# ProPrj_USB_Connector_2025-08-25.net
KiCad netlist of a schematic drawn in EasyEDA Pro
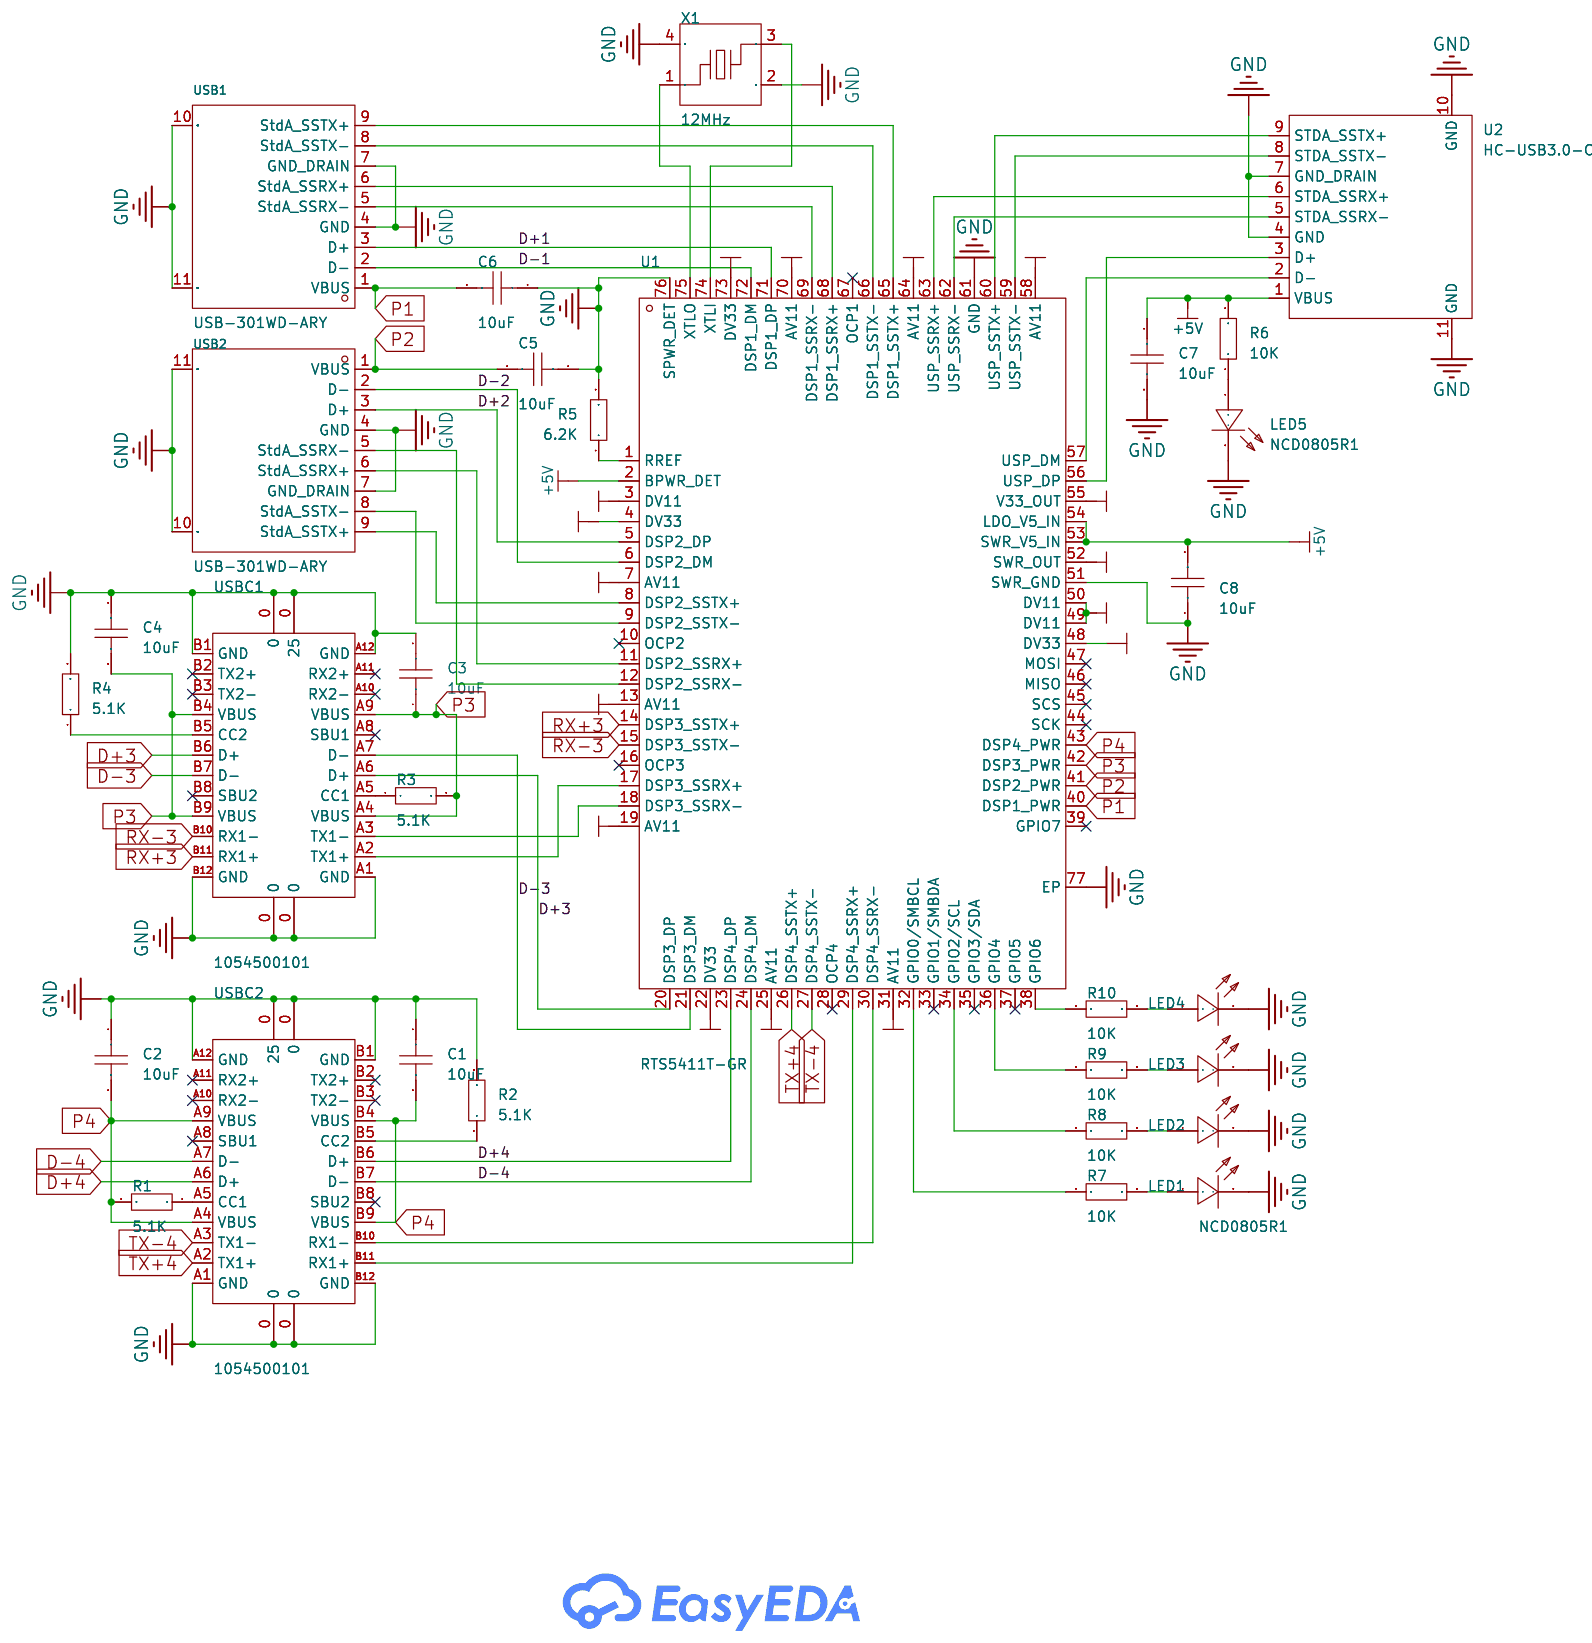
[diagram p0: schematic sheet]

(export (version "E")
  (design (tool "Eeschema 10.0.6"))
  (components
    (comp (ref "C1")
      (value "10uF")
      (footprint "easyedapro:C0603")
      (libsource (lib "easyedapro") (part "CAP"))
    )
    (comp (ref "C2")
      (value "10uF")
      (footprint "easyedapro:C0603")
      (libsource (lib "easyedapro") (part "CAP"))
    )
    (comp (ref "C3")
      (value "10uF")
      (footprint "easyedapro:C0603")
      (libsource (lib "easyedapro") (part "CAP"))
    )
    (comp (ref "C4")
      (value "10uF")
      (footprint "easyedapro:C0603")
      (libsource (lib "easyedapro") (part "CAP"))
    )
    (comp (ref "C5")
      (value "10uF")
      (footprint "easyedapro:C0603")
      (libsource (lib "easyedapro") (part "CAP"))
    )
    (comp (ref "C6")
      (value "10uF")
      (footprint "easyedapro:C0603")
      (libsource (lib "easyedapro") (part "CAP"))
    )
    (comp (ref "C7")
      (value "10uF")
      (footprint "easyedapro:C0603")
      (libsource (lib "easyedapro") (part "CAP"))
    )
    (comp (ref "C8")
      (value "10uF")
      (footprint "easyedapro:C0603")
      (libsource (lib "easyedapro") (part "CAP"))
    )
    (comp (ref "LED1")
      (value "NCD0805R1")
      (footprint "easyedapro:LED0805-R-RD")
      (fields (field (name "Manufacturer") "国星光电"))
      (libsource (lib "easyedapro") (part "FC-2012HRK-620D"))
    )
    (comp (ref "LED2")
      (value "NCD0805R1")
      (footprint "easyedapro:LED0805-R-RD")
      (fields (field (name "Manufacturer") "国星光电"))
      (libsource (lib "easyedapro") (part "FC-2012HRK-620D"))
    )
    (comp (ref "LED3")
      (value "NCD0805R1")
      (footprint "easyedapro:LED0805-R-RD")
      (fields (field (name "Manufacturer") "国星光电"))
      (libsource (lib "easyedapro") (part "FC-2012HRK-620D"))
    )
    (comp (ref "LED4")
      (value "NCD0805R1")
      (footprint "easyedapro:LED0805-R-RD")
      (fields (field (name "Manufacturer") "国星光电"))
      (libsource (lib "easyedapro") (part "FC-2012HRK-620D"))
    )
    (comp (ref "LED5")
      (value "NCD0805R1")
      (footprint "easyedapro:LED0805-R-RD")
      (fields (field (name "Manufacturer") "国星光电"))
      (libsource (lib "easyedapro") (part "FC-2012HRK-620D"))
    )
    (comp (ref "R1")
      (value "5.1K")
      (footprint "easyedapro:R0603")
      (libsource (lib "easyedapro") (part "Res"))
    )
    (comp (ref "R2")
      (value "5.1K")
      (footprint "easyedapro:R0603")
      (libsource (lib "easyedapro") (part "Res"))
    )
    (comp (ref "R3")
      (value "5.1K")
      (footprint "easyedapro:R0603")
      (libsource (lib "easyedapro") (part "Res"))
    )
    (comp (ref "R4")
      (value "5.1K")
      (footprint "easyedapro:R0603")
      (libsource (lib "easyedapro") (part "Res"))
    )
    (comp (ref "R5")
      (value "6.2K")
      (footprint "easyedapro:R0603")
      (libsource (lib "easyedapro") (part "Res"))
    )
    (comp (ref "R6") (value "10K") (footprint "easyedapro:R0603") (libsource (lib "easyedapro") (part "Res")))
    (comp (ref "R7") (value "10K") (footprint "easyedapro:R0603") (libsource (lib "easyedapro") (part "Res")))
    (comp (ref "R8") (value "10K") (footprint "easyedapro:R0603") (libsource (lib "easyedapro") (part "Res")))
    (comp (ref "R9") (value "10K") (footprint "easyedapro:R0603") (libsource (lib "easyedapro") (part "Res")))
    (comp (ref "R10")
      (value "10K")
      (footprint "easyedapro:R0603")
      (libsource (lib "easyedapro") (part "Res"))
    )
    (comp (ref "U1")
      (value "RTS5411T-GR")
      (footprint "easyedapro:QFN-76_L9.0-W9.0-P0.40-BL-EP5.4")
      (fields (field (name "Manufacturer") "REALTEK(瑞昱)"))
      (libsource (lib "easyedapro") (part "RTS5411T-GR"))
    )
    (comp (ref "U2")
      (value "HC-USB3.0-C26")
      (footprint "easyedapro:USB-3.0-A-SMD_HC-USB3.0-C26")
      (fields (field (name "Manufacturer") "HC(虹成电子)"))
      (libsource (lib "easyedapro") (part "HC-USB3.0-C26"))
    )
    (comp (ref "USB1")
      (value "USB-301WD-ARY")
      (footprint "easyedapro:USB-TH_XUNPU_USB-301WD-ARY")
      (fields (field (name "Manufacturer") "XUNPU(讯普)"))
      (libsource (lib "easyedapro") (part "USB-301WD-ARY"))
    )
    (comp (ref "USB2")
      (value "USB-301WD-ARY")
      (footprint "easyedapro:USB-TH_XUNPU_USB-301WD-ARY")
      (fields (field (name "Manufacturer") "XUNPU(讯普)"))
      (libsource (lib "easyedapro") (part "USB-301WD-ARY"))
    )
    (comp (ref "USBC1")
      (value "1054500101")
      (footprint "easyedapro:USB-C-SMD_TYPE-C-USB-18")
      (fields (field (name "Manufacturer") "MOLEX"))
      (libsource (lib "easyedapro") (part "105450-0101"))
    )
    (comp (ref "USBC2")
      (value "1054500101")
      (footprint "easyedapro:USB-C-SMD_TYPE-C-USB-18")
      (fields (field (name "Manufacturer") "MOLEX"))
      (libsource (lib "easyedapro") (part "105450-0101"))
    )
    (comp (ref "X1")
      (value "12MHz")
      (footprint "easyedapro:CRYSTAL-SMD_4P-L3.2-W2.5-BL-1")
      (fields
        (field (name "Manufacturer Part") "XL2EL89COI-111YLC-12M")
        (field (name "Manufacturer") "YXC(扬兴晶振)")
      )
      (libsource (lib "easyedapro") (part "XL2EL89COI-111YLC-12M"))
    )
  )
  (nets
    (net (code "1") (name "+1V1") (class "Default")
      (node (ref "U1") (pin "13") (pinfunction "AV11_13") (pintype "unspecified"))
      (node (ref "U1") (pin "19") (pinfunction "AV11_19") (pintype "unspecified"))
      (node (ref "U1") (pin "25") (pinfunction "AV11_25") (pintype "unspecified"))
      (node (ref "U1") (pin "3") (pinfunction "DV11_3") (pintype "unspecified"))
      (node (ref "U1") (pin "31") (pinfunction "AV11_31") (pintype "unspecified"))
      (node (ref "U1") (pin "49") (pinfunction "DV11_49") (pintype "unspecified"))
      (node (ref "U1") (pin "50") (pinfunction "DV11_50") (pintype "unspecified"))
      (node (ref "U1") (pin "52") (pinfunction "SWR_OUT_52") (pintype "unspecified"))
      (node (ref "U1") (pin "58") (pinfunction "AV11_58") (pintype "unspecified"))
      (node (ref "U1") (pin "64") (pinfunction "AV11_64") (pintype "unspecified"))
      (node (ref "U1") (pin "7") (pinfunction "AV11_7") (pintype "unspecified"))
      (node (ref "U1") (pin "70") (pinfunction "AV11_70") (pintype "unspecified"))
    )
    (net (code "2") (name "+3V3") (class "Default")
      (node (ref "U1") (pin "22") (pinfunction "DV33_22") (pintype "unspecified"))
      (node (ref "U1") (pin "4") (pinfunction "DV33_4") (pintype "unspecified"))
      (node (ref "U1") (pin "48") (pinfunction "DV33_48") (pintype "unspecified"))
      (node (ref "U1") (pin "55") (pinfunction "V33_OUT_55") (pintype "unspecified"))
      (node (ref "U1") (pin "73") (pinfunction "DV33_73") (pintype "unspecified"))
    )
    (net (code "3") (name "+5V") (class "Default")
      (node (ref "C7") (pin "1") (pinfunction "1_1") (pintype "input"))
      (node (ref "C8") (pin "2") (pinfunction "2_2") (pintype "input"))
      (node (ref "R6") (pin "2") (pinfunction "2_2") (pintype "input"))
      (node (ref "U1") (pin "2") (pinfunction "BPWR_DET_2") (pintype "unspecified"))
      (node (ref "U1") (pin "53") (pinfunction "SWR_V5_IN_53") (pintype "unspecified"))
      (node (ref "U1") (pin "54") (pinfunction "LDO_V5_IN_54") (pintype "unspecified"))
      (node (ref "U2") (pin "1") (pinfunction "VBUS_1") (pintype "unspecified"))
    )
    (net (code "4") (name "/D+1") (class "Default")
      (node (ref "U1") (pin "71") (pinfunction "DSP1_DP_71") (pintype "unspecified"))
      (node (ref "USB1") (pin "3") (pinfunction "D+_3") (pintype "input"))
    )
    (net (code "5") (name "/D+2") (class "Default")
      (node (ref "U1") (pin "5") (pinfunction "DSP2_DP_5") (pintype "unspecified"))
      (node (ref "USB2") (pin "3") (pinfunction "D+_3") (pintype "input"))
    )
    (net (code "6") (name "/D-1") (class "Default")
      (node (ref "U1") (pin "72") (pinfunction "DSP1_DM_72") (pintype "unspecified"))
      (node (ref "USB1") (pin "2") (pinfunction "D-_2") (pintype "input"))
    )
    (net (code "7") (name "/D-2") (class "Default")
      (node (ref "U1") (pin "6") (pinfunction "DSP2_DM_6") (pintype "unspecified"))
      (node (ref "USB2") (pin "2") (pinfunction "D-_2") (pintype "input"))
    )
    (net (code "8") (name "D+3") (class "Default")
      (node (ref "U1") (pin "20") (pinfunction "DSP3_DP_20") (pintype "unspecified"))
      (node (ref "USBC1") (pin "A6") (pinfunction "D+_A6") (pintype "unspecified"))
      (node (ref "USBC1") (pin "B6") (pinfunction "D+_B6") (pintype "unspecified"))
    )
    (net (code "9") (name "D+4") (class "Default")
      (node (ref "U1") (pin "23") (pinfunction "DSP4_DP_23") (pintype "unspecified"))
      (node (ref "USBC2") (pin "A6") (pinfunction "D+_A6") (pintype "unspecified"))
      (node (ref "USBC2") (pin "B6") (pinfunction "D+_B6") (pintype "unspecified"))
    )
    (net (code "10") (name "D-3") (class "Default")
      (node (ref "U1") (pin "21") (pinfunction "DSP3_DM_21") (pintype "unspecified"))
      (node (ref "USBC1") (pin "A7") (pinfunction "D-_A7") (pintype "unspecified"))
      (node (ref "USBC1") (pin "B7") (pinfunction "D-_B7") (pintype "unspecified"))
    )
    (net (code "11") (name "D-4") (class "Default")
      (node (ref "U1") (pin "24") (pinfunction "DSP4_DM_24") (pintype "unspecified"))
      (node (ref "USBC2") (pin "A7") (pinfunction "D-_A7") (pintype "unspecified"))
      (node (ref "USBC2") (pin "B7") (pinfunction "D-_B7") (pintype "unspecified"))
    )
    (net (code "12") (name "GND") (class "Default")
      (node (ref "C1") (pin "1") (pinfunction "1_1") (pintype "input"))
      (node (ref "C2") (pin "1") (pinfunction "1_1") (pintype "input"))
      (node (ref "C3") (pin "2") (pinfunction "2_2") (pintype "input"))
      (node (ref "C4") (pin "1") (pinfunction "1_1") (pintype "input"))
      (node (ref "C5") (pin "1") (pinfunction "1_1") (pintype "input"))
      (node (ref "C6") (pin "1") (pinfunction "1_1") (pintype "input"))
      (node (ref "C7") (pin "2") (pinfunction "2_2") (pintype "input"))
      (node (ref "C8") (pin "1") (pinfunction "1_1") (pintype "input"))
      (node (ref "LED1") (pin "2") (pinfunction "-_2") (pintype "unspecified"))
      (node (ref "LED2") (pin "2") (pinfunction "-_2") (pintype "unspecified"))
      (node (ref "LED3") (pin "2") (pinfunction "-_2") (pintype "unspecified"))
      (node (ref "LED4") (pin "2") (pinfunction "-_2") (pintype "unspecified"))
      (node (ref "LED5") (pin "2") (pinfunction "-_2") (pintype "unspecified"))
      (node (ref "R2") (pin "2") (pinfunction "2_2") (pintype "input"))
      (node (ref "R4") (pin "2") (pinfunction "2_2") (pintype "input"))
      (node (ref "R5") (pin "2") (pinfunction "2_2") (pintype "input"))
      (node (ref "U1") (pin "51") (pinfunction "SWR_GND_51") (pintype "unspecified"))
      (node (ref "U1") (pin "61") (pinfunction "GND_61") (pintype "unspecified"))
      (node (ref "U1") (pin "76") (pinfunction "SPWR_DET_76") (pintype "unspecified"))
      (node (ref "U1") (pin "77") (pinfunction "EP_77") (pintype "unspecified"))
      (node (ref "U2") (pin "10") (pinfunction "GND_10") (pintype "unspecified"))
      (node (ref "U2") (pin "11") (pinfunction "GND_11") (pintype "unspecified"))
      (node (ref "U2") (pin "4") (pinfunction "GND_4") (pintype "unspecified"))
      (node (ref "U2") (pin "7") (pinfunction "GND_DRAIN_7") (pintype "unspecified"))
      (node (ref "USB1") (pin "10") (pinfunction "SHIELD_10") (pintype "input"))
      (node (ref "USB1") (pin "11") (pinfunction "SHIELD_11") (pintype "input"))
      (node (ref "USB1") (pin "4") (pinfunction "GND_4") (pintype "input"))
      (node (ref "USB1") (pin "7") (pinfunction "GND_DRAIN_7") (pintype "input"))
      (node (ref "USB2") (pin "10") (pinfunction "SHIELD_10") (pintype "input"))
      (node (ref "USB2") (pin "11") (pinfunction "SHIELD_11") (pintype "input"))
      (node (ref "USB2") (pin "4") (pinfunction "GND_4") (pintype "input"))
      (node (ref "USB2") (pin "7") (pinfunction "GND_DRAIN_7") (pintype "input"))
      (node (ref "USBC1") (pin "0") (pinfunction "0_0") (pintype "unspecified"))
      (node (ref "USBC1") (pin "A1") (pinfunction "GND_A1") (pintype "unspecified"))
      (node (ref "USBC1") (pin "A12") (pinfunction "GND_A12") (pintype "unspecified"))
      (node (ref "USBC1") (pin "B1") (pinfunction "GND_B1") (pintype "unspecified"))
      (node (ref "USBC1") (pin "B12") (pinfunction "GND_B12") (pintype "unspecified"))
      (node (ref "USBC2") (pin "0") (pinfunction "0_0") (pintype "unspecified"))
      (node (ref "USBC2") (pin "A1") (pinfunction "GND_A1") (pintype "unspecified"))
      (node (ref "USBC2") (pin "A12") (pinfunction "GND_A12") (pintype "unspecified"))
      (node (ref "USBC2") (pin "B1") (pinfunction "GND_B1") (pintype "unspecified"))
      (node (ref "USBC2") (pin "B12") (pinfunction "GND_B12") (pintype "unspecified"))
      (node (ref "X1") (pin "2") (pinfunction "GND_2") (pintype "input"))
      (node (ref "X1") (pin "4") (pinfunction "GND_4") (pintype "input"))
    )
    (net (code "13") (name "Net-(LED1-+)") (class "Default")
      (node (ref "LED1") (pin "1") (pinfunction "+_1") (pintype "unspecified"))
      (node (ref "R7") (pin "2") (pinfunction "2_2") (pintype "input"))
    )
    (net (code "14") (name "Net-(LED2-+)") (class "Default")
      (node (ref "LED2") (pin "1") (pinfunction "+_1") (pintype "unspecified"))
      (node (ref "R8") (pin "2") (pinfunction "2_2") (pintype "input"))
    )
    (net (code "15") (name "Net-(LED3-+)") (class "Default")
      (node (ref "LED3") (pin "1") (pinfunction "+_1") (pintype "unspecified"))
      (node (ref "R9") (pin "2") (pinfunction "2_2") (pintype "input"))
    )
    (net (code "16") (name "Net-(LED4-+)") (class "Default")
      (node (ref "LED4") (pin "1") (pinfunction "+_1") (pintype "unspecified"))
      (node (ref "R10") (pin "2") (pinfunction "2_2") (pintype "input"))
    )
    (net (code "17") (name "Net-(LED5-+)") (class "Default")
      (node (ref "LED5") (pin "1") (pinfunction "+_1") (pintype "unspecified"))
      (node (ref "R6") (pin "1") (pinfunction "1_1") (pintype "input"))
    )
    (net (code "18") (name "Net-(U1-DSP1_SSRX+)") (class "Default")
      (node (ref "U1") (pin "68") (pinfunction "DSP1_SSRX+_68") (pintype "unspecified"))
      (node (ref "USB1") (pin "6") (pinfunction "StdA_SSRX+_6") (pintype "input"))
    )
    (net (code "19") (name "Net-(U1-DSP1_SSRX-)") (class "Default")
      (node (ref "U1") (pin "69") (pinfunction "DSP1_SSRX-_69") (pintype "unspecified"))
      (node (ref "USB1") (pin "5") (pinfunction "StdA_SSRX-_5") (pintype "input"))
    )
    (net (code "20") (name "Net-(U1-DSP1_SSTX+)") (class "Default")
      (node (ref "U1") (pin "65") (pinfunction "DSP1_SSTX+_65") (pintype "unspecified"))
      (node (ref "USB1") (pin "9") (pinfunction "StdA_SSTX+_9") (pintype "input"))
    )
    (net (code "21") (name "Net-(U1-DSP1_SSTX-)") (class "Default")
      (node (ref "U1") (pin "66") (pinfunction "DSP1_SSTX-_66") (pintype "unspecified"))
      (node (ref "USB1") (pin "8") (pinfunction "StdA_SSTX-_8") (pintype "input"))
    )
    (net (code "22") (name "Net-(U1-DSP2_SSRX+)") (class "Default")
      (node (ref "U1") (pin "11") (pinfunction "DSP2_SSRX+_11") (pintype "unspecified"))
      (node (ref "USB2") (pin "6") (pinfunction "StdA_SSRX+_6") (pintype "input"))
    )
    (net (code "23") (name "Net-(U1-DSP2_SSRX-)") (class "Default")
      (node (ref "U1") (pin "12") (pinfunction "DSP2_SSRX-_12") (pintype "unspecified"))
      (node (ref "USB2") (pin "5") (pinfunction "StdA_SSRX-_5") (pintype "input"))
    )
    (net (code "24") (name "Net-(U1-DSP2_SSTX+)") (class "Default")
      (node (ref "U1") (pin "8") (pinfunction "DSP2_SSTX+_8") (pintype "unspecified"))
      (node (ref "USB2") (pin "9") (pinfunction "StdA_SSTX+_9") (pintype "input"))
    )
    (net (code "25") (name "Net-(U1-DSP2_SSTX-)") (class "Default")
      (node (ref "U1") (pin "9") (pinfunction "DSP2_SSTX-_9") (pintype "unspecified"))
      (node (ref "USB2") (pin "8") (pinfunction "StdA_SSTX-_8") (pintype "input"))
    )
    (net (code "26") (name "Net-(U1-DSP3_SSRX+)") (class "Default")
      (node (ref "U1") (pin "17") (pinfunction "DSP3_SSRX+_17") (pintype "unspecified"))
      (node (ref "USBC1") (pin "A2") (pinfunction "TX1+_A2") (pintype "unspecified"))
    )
    (net (code "27") (name "Net-(U1-DSP3_SSRX-)") (class "Default")
      (node (ref "U1") (pin "18") (pinfunction "DSP3_SSRX-_18") (pintype "unspecified"))
      (node (ref "USBC1") (pin "A3") (pinfunction "TX1-_A3") (pintype "unspecified"))
    )
    (net (code "28") (name "Net-(U1-DSP4_SSRX+)") (class "Default")
      (node (ref "U1") (pin "29") (pinfunction "DSP4_SSRX+_29") (pintype "unspecified"))
      (node (ref "USBC2") (pin "B11") (pinfunction "RX1+_B11") (pintype "unspecified"))
    )
    (net (code "29") (name "Net-(U1-DSP4_SSRX-)") (class "Default")
      (node (ref "U1") (pin "30") (pinfunction "DSP4_SSRX-_30") (pintype "unspecified"))
      (node (ref "USBC2") (pin "B10") (pinfunction "RX1-_B10") (pintype "unspecified"))
    )
    (net (code "30") (name "Net-(U1-GPIO0{slash}SMBCL)") (class "Default")
      (node (ref "R7") (pin "1") (pinfunction "1_1") (pintype "input"))
      (node (ref "U1") (pin "32") (pinfunction "GPIO0/SMBCL_32") (pintype "unspecified"))
    )
    (net (code "31") (name "Net-(U1-GPIO2{slash}SCL)") (class "Default")
      (node (ref "R8") (pin "1") (pinfunction "1_1") (pintype "input"))
      (node (ref "U1") (pin "34") (pinfunction "GPIO2/SCL_34") (pintype "unspecified"))
    )
    (net (code "32") (name "Net-(U1-GPIO4)") (class "Default")
      (node (ref "R9") (pin "1") (pinfunction "1_1") (pintype "input"))
      (node (ref "U1") (pin "36") (pinfunction "GPIO4_36") (pintype "unspecified"))
    )
    (net (code "33") (name "Net-(U1-GPIO6)") (class "Default")
      (node (ref "R10") (pin "1") (pinfunction "1_1") (pintype "input"))
      (node (ref "U1") (pin "38") (pinfunction "GPIO6_38") (pintype "unspecified"))
    )
    (net (code "34") (name "Net-(U1-RREF)") (class "Default")
      (node (ref "R5") (pin "1") (pinfunction "1_1") (pintype "input"))
      (node (ref "U1") (pin "1") (pinfunction "RREF_1") (pintype "unspecified"))
    )
    (net (code "35") (name "Net-(U1-USP_DM)") (class "Default")
      (node (ref "U1") (pin "57") (pinfunction "USP_DM_57") (pintype "unspecified"))
      (node (ref "U2") (pin "2") (pinfunction "D-_2") (pintype "unspecified"))
    )
    (net (code "36") (name "Net-(U1-USP_DP)") (class "Default")
      (node (ref "U1") (pin "56") (pinfunction "USP_DP_56") (pintype "unspecified"))
      (node (ref "U2") (pin "3") (pinfunction "D+_3") (pintype "unspecified"))
    )
    (net (code "37") (name "Net-(U1-USP_SSRX+)") (class "Default")
      (node (ref "U1") (pin "63") (pinfunction "USP_SSRX+_63") (pintype "unspecified"))
      (node (ref "U2") (pin "6") (pinfunction "STDA_SSRX+_6") (pintype "unspecified"))
    )
    (net (code "38") (name "Net-(U1-USP_SSRX-)") (class "Default")
      (node (ref "U1") (pin "62") (pinfunction "USP_SSRX-_62") (pintype "unspecified"))
      (node (ref "U2") (pin "5") (pinfunction "STDA_SSRX-_5") (pintype "unspecified"))
    )
    (net (code "39") (name "Net-(U1-USP_SSTX+)") (class "Default")
      (node (ref "U1") (pin "60") (pinfunction "USP_SSTX+_60") (pintype "unspecified"))
      (node (ref "U2") (pin "9") (pinfunction "STDA_SSTX+_9") (pintype "unspecified"))
    )
    (net (code "40") (name "Net-(U1-USP_SSTX-)") (class "Default")
      (node (ref "U1") (pin "59") (pinfunction "USP_SSTX-_59") (pintype "unspecified"))
      (node (ref "U2") (pin "8") (pinfunction "STDA_SSTX-_8") (pintype "unspecified"))
    )
    (net (code "41") (name "Net-(U1-XTLI)") (class "Default")
      (node (ref "U1") (pin "74") (pinfunction "XTLI_74") (pintype "unspecified"))
      (node (ref "X1") (pin "3") (pinfunction "3_3") (pintype "input"))
    )
    (net (code "42") (name "Net-(U1-XTLO)") (class "Default")
      (node (ref "U1") (pin "75") (pinfunction "XTLO_75") (pintype "unspecified"))
      (node (ref "X1") (pin "1") (pinfunction "1_1") (pintype "input"))
    )
    (net (code "43") (name "Net-(USBC1-CC1)") (class "Default")
      (node (ref "R3") (pin "1") (pinfunction "1_1") (pintype "input"))
      (node (ref "USBC1") (pin "A5") (pinfunction "CC1_A5") (pintype "unspecified"))
    )
    (net (code "44") (name "Net-(USBC1-CC2)") (class "Default")
      (node (ref "R4") (pin "1") (pinfunction "1_1") (pintype "input"))
      (node (ref "USBC1") (pin "B5") (pinfunction "CC2_B5") (pintype "unspecified"))
    )
    (net (code "45") (name "Net-(USBC2-CC1)") (class "Default")
      (node (ref "R1") (pin "1") (pinfunction "1_1") (pintype "input"))
      (node (ref "USBC2") (pin "A5") (pinfunction "CC1_A5") (pintype "unspecified"))
    )
    (net (code "46") (name "Net-(USBC2-CC2)") (class "Default")
      (node (ref "R2") (pin "1") (pinfunction "1_1") (pintype "input"))
      (node (ref "USBC2") (pin "B5") (pinfunction "CC2_B5") (pintype "unspecified"))
    )
    (net (code "47") (name "P1") (class "Default")
      (node (ref "C6") (pin "2") (pinfunction "2_2") (pintype "input"))
      (node (ref "U1") (pin "40") (pinfunction "DSP1_PWR_40") (pintype "unspecified"))
      (node (ref "USB1") (pin "1") (pinfunction "VBUS_1") (pintype "input"))
    )
    (net (code "48") (name "P2") (class "Default")
      (node (ref "C5") (pin "2") (pinfunction "2_2") (pintype "input"))
      (node (ref "U1") (pin "41") (pinfunction "DSP2_PWR_41") (pintype "unspecified"))
      (node (ref "USB2") (pin "1") (pinfunction "VBUS_1") (pintype "input"))
    )
    (net (code "49") (name "P3") (class "Default")
      (node (ref "C3") (pin "1") (pinfunction "1_1") (pintype "input"))
      (node (ref "C4") (pin "2") (pinfunction "2_2") (pintype "input"))
      (node (ref "R3") (pin "2") (pinfunction "2_2") (pintype "input"))
      (node (ref "U1") (pin "42") (pinfunction "DSP3_PWR_42") (pintype "unspecified"))
      (node (ref "USBC1") (pin "A4") (pinfunction "VBUS_A4") (pintype "unspecified"))
      (node (ref "USBC1") (pin "A9") (pinfunction "VBUS_A9") (pintype "unspecified"))
      (node (ref "USBC1") (pin "B4") (pinfunction "VBUS_B4") (pintype "unspecified"))
      (node (ref "USBC1") (pin "B9") (pinfunction "VBUS_B9") (pintype "unspecified"))
    )
    (net (code "50") (name "P4") (class "Default")
      (node (ref "C1") (pin "2") (pinfunction "2_2") (pintype "input"))
      (node (ref "C2") (pin "2") (pinfunction "2_2") (pintype "input"))
      (node (ref "R1") (pin "2") (pinfunction "2_2") (pintype "input"))
      (node (ref "U1") (pin "43") (pinfunction "DSP4_PWR_43") (pintype "unspecified"))
      (node (ref "USBC2") (pin "A4") (pinfunction "VBUS_A4") (pintype "unspecified"))
      (node (ref "USBC2") (pin "A9") (pinfunction "VBUS_A9") (pintype "unspecified"))
      (node (ref "USBC2") (pin "B4") (pinfunction "VBUS_B4") (pintype "unspecified"))
      (node (ref "USBC2") (pin "B9") (pinfunction "VBUS_B9") (pintype "unspecified"))
    )
    (net (code "51") (name "RX+3") (class "Default")
      (node (ref "U1") (pin "14") (pinfunction "DSP3_SSTX+_14") (pintype "unspecified"))
      (node (ref "USBC1") (pin "B11") (pinfunction "RX1+_B11") (pintype "unspecified"))
    )
    (net (code "52") (name "RX-3") (class "Default")
      (node (ref "U1") (pin "15") (pinfunction "DSP3_SSTX-_15") (pintype "unspecified"))
      (node (ref "USBC1") (pin "B10") (pinfunction "RX1-_B10") (pintype "unspecified"))
    )
    (net (code "53") (name "TX+4") (class "Default")
      (node (ref "U1") (pin "26") (pinfunction "DSP4_SSTX+_26") (pintype "unspecified"))
      (node (ref "USBC2") (pin "A2") (pinfunction "TX1+_A2") (pintype "unspecified"))
    )
    (net (code "54") (name "TX-4") (class "Default")
      (node (ref "U1") (pin "27") (pinfunction "DSP4_SSTX-_27") (pintype "unspecified"))
      (node (ref "USBC2") (pin "A3") (pinfunction "TX1-_A3") (pintype "unspecified"))
    )
    (net (code "55") (name "unconnected-(U1-GPIO1{slash}SMBDA-Pad33)") (class "Default")
      (node (ref "U1") (pin "33") (pinfunction "GPIO1/SMBDA_33") (pintype "unspecified+no_connect"))
    )
    (net (code "56") (name "unconnected-(U1-GPIO3{slash}SDA-Pad35)") (class "Default")
      (node (ref "U1") (pin "35") (pinfunction "GPIO3/SDA_35") (pintype "unspecified+no_connect"))
    )
    (net (code "57") (name "unconnected-(U1-GPIO5-Pad37)") (class "Default")
      (node (ref "U1") (pin "37") (pinfunction "GPIO5_37") (pintype "unspecified+no_connect"))
    )
    (net (code "58") (name "unconnected-(U1-GPIO7-Pad39)") (class "Default")
      (node (ref "U1") (pin "39") (pinfunction "GPIO7_39") (pintype "unspecified+no_connect"))
    )
    (net (code "59") (name "unconnected-(U1-MISO-Pad46)") (class "Default")
      (node (ref "U1") (pin "46") (pinfunction "MISO_46") (pintype "unspecified+no_connect"))
    )
    (net (code "60") (name "unconnected-(U1-MOSI-Pad47)") (class "Default")
      (node (ref "U1") (pin "47") (pinfunction "MOSI_47") (pintype "unspecified+no_connect"))
    )
    (net (code "61") (name "unconnected-(U1-OCP1-Pad67)") (class "Default")
      (node (ref "U1") (pin "67") (pinfunction "OCP1_67") (pintype "unspecified+no_connect"))
    )
    (net (code "62") (name "unconnected-(U1-OCP2-Pad10)") (class "Default")
      (node (ref "U1") (pin "10") (pinfunction "OCP2_10") (pintype "unspecified+no_connect"))
    )
    (net (code "63") (name "unconnected-(U1-OCP3-Pad16)") (class "Default")
      (node (ref "U1") (pin "16") (pinfunction "OCP3_16") (pintype "unspecified+no_connect"))
    )
    (net (code "64") (name "unconnected-(U1-OCP4-Pad28)") (class "Default")
      (node (ref "U1") (pin "28") (pinfunction "OCP4_28") (pintype "unspecified+no_connect"))
    )
    (net (code "65") (name "unconnected-(U1-SCK-Pad44)") (class "Default")
      (node (ref "U1") (pin "44") (pinfunction "SCK_44") (pintype "unspecified+no_connect"))
    )
    (net (code "66") (name "unconnected-(U1-SCS-Pad45)") (class "Default")
      (node (ref "U1") (pin "45") (pinfunction "SCS_45") (pintype "unspecified+no_connect"))
    )
    (net (code "67") (name "unconnected-(USBC1-RX2+-PadA11)") (class "Default")
      (node (ref "USBC1") (pin "A11") (pinfunction "RX2+_A11") (pintype "unspecified+no_connect"))
    )
    (net (code "68") (name "unconnected-(USBC1-RX2--PadA10)") (class "Default")
      (node (ref "USBC1") (pin "A10") (pinfunction "RX2-_A10") (pintype "unspecified+no_connect"))
    )
    (net (code "69") (name "unconnected-(USBC1-SBU1-PadA8)") (class "Default")
      (node (ref "USBC1") (pin "A8") (pinfunction "SBU1_A8") (pintype "unspecified+no_connect"))
    )
    (net (code "70") (name "unconnected-(USBC1-SBU2-PadB8)") (class "Default")
      (node (ref "USBC1") (pin "B8") (pinfunction "SBU2_B8") (pintype "unspecified+no_connect"))
    )
    (net (code "71") (name "unconnected-(USBC1-TX2+-PadB2)") (class "Default")
      (node (ref "USBC1") (pin "B2") (pinfunction "TX2+_B2") (pintype "unspecified+no_connect"))
    )
    (net (code "72") (name "unconnected-(USBC1-TX2--PadB3)") (class "Default")
      (node (ref "USBC1") (pin "B3") (pinfunction "TX2-_B3") (pintype "unspecified+no_connect"))
    )
    (net (code "73") (name "unconnected-(USBC2-RX2+-PadA11)") (class "Default")
      (node (ref "USBC2") (pin "A11") (pinfunction "RX2+_A11") (pintype "unspecified+no_connect"))
    )
    (net (code "74") (name "unconnected-(USBC2-RX2--PadA10)") (class "Default")
      (node (ref "USBC2") (pin "A10") (pinfunction "RX2-_A10") (pintype "unspecified+no_connect"))
    )
    (net (code "75") (name "unconnected-(USBC2-SBU1-PadA8)") (class "Default")
      (node (ref "USBC2") (pin "A8") (pinfunction "SBU1_A8") (pintype "unspecified+no_connect"))
    )
    (net (code "76") (name "unconnected-(USBC2-SBU2-PadB8)") (class "Default")
      (node (ref "USBC2") (pin "B8") (pinfunction "SBU2_B8") (pintype "unspecified+no_connect"))
    )
    (net (code "77") (name "unconnected-(USBC2-TX2+-PadB2)") (class "Default")
      (node (ref "USBC2") (pin "B2") (pinfunction "TX2+_B2") (pintype "unspecified+no_connect"))
    )
    (net (code "78") (name "unconnected-(USBC2-TX2--PadB3)") (class "Default")
      (node (ref "USBC2") (pin "B3") (pinfunction "TX2-_B3") (pintype "unspecified+no_connect"))
    )
  )
)
